# 05-SD_Card.net
KiCad netlist of a schematic drawn in Altium Designer
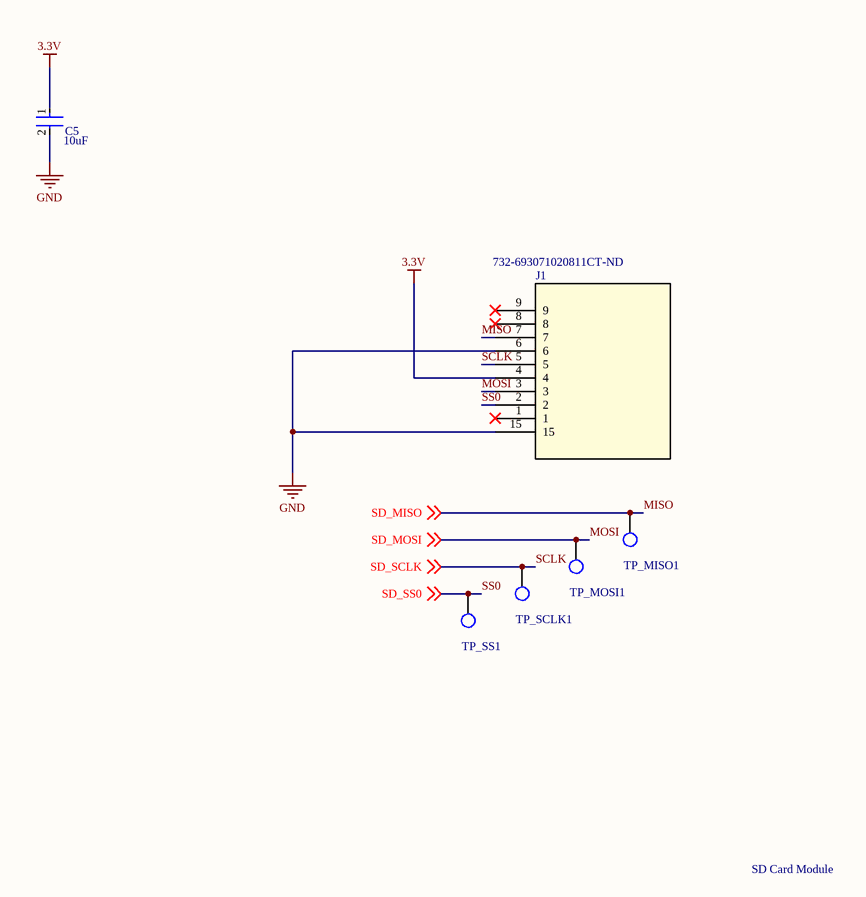
[diagram p0: 05-SD_Card.SchDoc]

(export (version "E")
  (design (tool "Eeschema 10.0.6"))
  (components
    (comp (ref "C5")
      (value "CL21A106KQCLNNC")
      (footprint "FP-CL21-IPC_B")
      (description "CL21 Series 0805 10uF 6.3V ±10% Tolerance X5R Multilayer Ceramic Chip Capacitor")
      (fields (field (name "CAPACITANCE") "10uF") (field (name "TOLERANCE") "10%"))
      (libsource (lib "Altium Content Vault") (part "b4654b650e69147ec39a6b967a45e02"))
    )
    (comp (ref "J1")
      (value "~")
      (footprint "CONN9_020811_WRE")
      (description "No Description Available")
      (fields
        (field (name "MANUFACTURER_PART_NUMBER") "693071020811")
        (field (name "SUPPLIER PART NUMBER 1") "732-693071020811CT-ND")
        (field (name "COPYRIGHT") "Copyright (C) 2022 Ultra Librarian. All rights reserved.")
      )
      (libsource (lib "team6") (part "693071020811"))
    )
    (comp (ref "TP_MISO1")
      (value "TP_1206")
      (footprint "TP-SMC-1206")
      (description "Test Point SMD 1206")
      (fields
        (field (name "MANUFACTURER") "TE Connectivity (Tyco Electronics)")
        (field (name "MANUFACTURER PART NUMBER") "1625854-1")
      )
      (libsource (lib "ECE453-F22-Power") (part "TP_1206"))
    )
    (comp (ref "TP_MOSI1")
      (value "TP_1206")
      (footprint "TP-SMC-1206")
      (description "Test Point SMD 1206")
      (fields
        (field (name "MANUFACTURER") "TE Connectivity (Tyco Electronics)")
        (field (name "MANUFACTURER PART NUMBER") "1625854-1")
      )
      (libsource (lib "ECE453-F22-Power") (part "TP_1206"))
    )
    (comp (ref "TP_SCLK1")
      (value "TP_1206")
      (footprint "TP-SMC-1206")
      (description "Test Point SMD 1206")
      (fields
        (field (name "MANUFACTURER") "TE Connectivity (Tyco Electronics)")
        (field (name "MANUFACTURER PART NUMBER") "1625854-1")
      )
      (libsource (lib "ECE453-F22-Power") (part "TP_1206"))
    )
    (comp (ref "TP_SS1")
      (value "TP_1206")
      (footprint "TP-SMC-1206")
      (description "Test Point SMD 1206")
      (fields
        (field (name "MANUFACTURER") "TE Connectivity (Tyco Electronics)")
        (field (name "MANUFACTURER PART NUMBER") "1625854-1")
      )
      (libsource (lib "ECE453-F22-Power") (part "TP_1206"))
    )
  )
  (nets
    (net (code "1") (name "3.3V") (class "Default")
      (node (ref "C5") (pin "1") (pinfunction "1_1") (pintype "passive"))
      (node (ref "J1") (pin "4") (pinfunction "4_4") (pintype "passive"))
    )
    (net (code "2") (name "GND") (class "Default")
      (node (ref "C5") (pin "2") (pinfunction "2_2") (pintype "passive"))
      (node (ref "J1") (pin "15") (pinfunction "15_15") (pintype "passive"))
      (node (ref "J1") (pin "6") (pinfunction "6_6") (pintype "passive"))
    )
    (net (code "3") (name "SD_MISO") (class "Default")
      (node (ref "J1") (pin "7") (pinfunction "7_7") (pintype "passive"))
      (node (ref "TP_MISO1") (pin "1") (pintype "passive"))
    )
    (net (code "4") (name "SD_MOSI") (class "Default")
      (node (ref "J1") (pin "3") (pinfunction "3_3") (pintype "passive"))
      (node (ref "TP_MOSI1") (pin "1") (pintype "passive"))
    )
    (net (code "5") (name "SD_SCLK") (class "Default")
      (node (ref "J1") (pin "5") (pinfunction "5_5") (pintype "passive"))
      (node (ref "TP_SCLK1") (pin "1") (pintype "passive"))
    )
    (net (code "6") (name "SD_SS0") (class "Default")
      (node (ref "J1") (pin "2") (pinfunction "2_2") (pintype "passive"))
      (node (ref "TP_SS1") (pin "1") (pintype "passive"))
    )
    (net (code "7") (name "unconnected-(J1-Pad1)") (class "Default")
      (node (ref "J1") (pin "1") (pinfunction "1_1") (pintype "passive+no_connect"))
    )
    (net (code "8") (name "unconnected-(J1-Pad8)") (class "Default")
      (node (ref "J1") (pin "8") (pinfunction "8_8") (pintype "passive+no_connect"))
    )
    (net (code "9") (name "unconnected-(J1-Pad9)") (class "Default")
      (node (ref "J1") (pin "9") (pinfunction "9_9") (pintype "passive+no_connect"))
    )
  )
)
